# TP5400__2021-06-20.net
KiCad netlist of a schematic drawn in EasyEDA
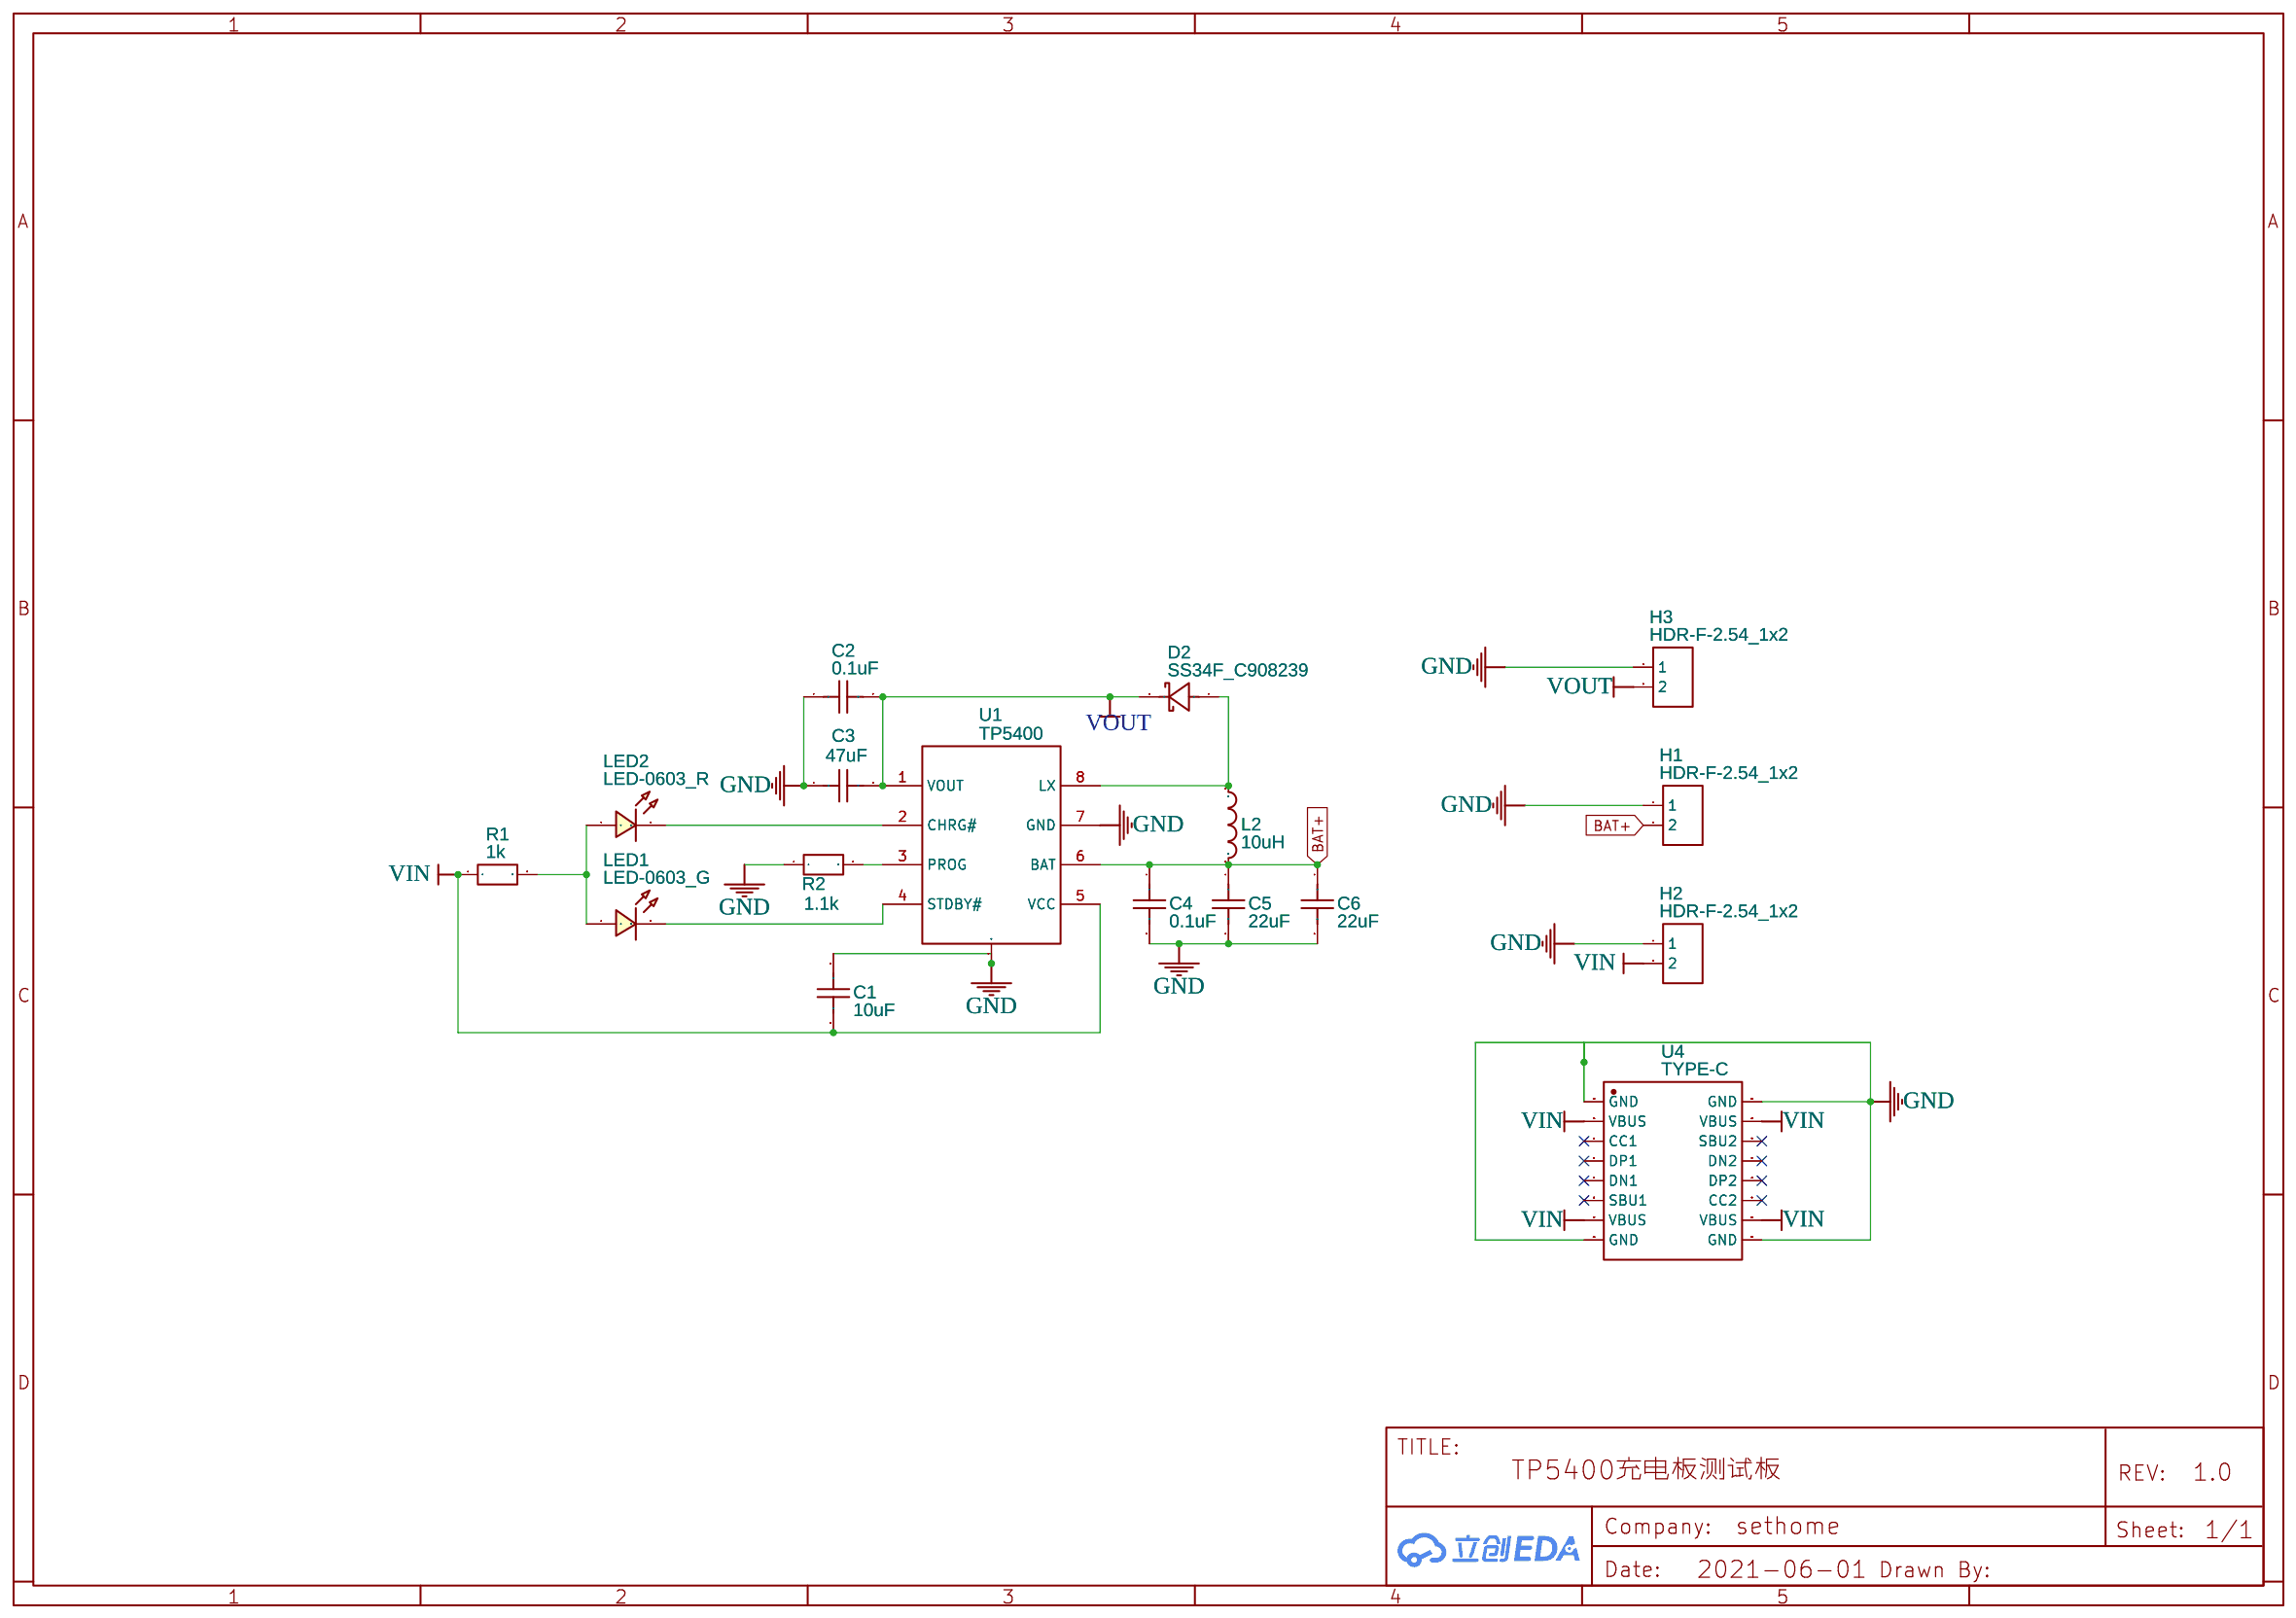
[diagram p0: schematic sheet]

(export (version "E")
  (design (tool "Eeschema 10.0.6"))
  (components
    (comp (ref "C1") (value "10uF") (libsource (lib "") (part "C_0603_US_1")))
    (comp (ref "C2") (value "0.1uF") (libsource (lib "") (part "C_0603_US")))
    (comp (ref "C3") (value "47uF") (libsource (lib "") (part "C_1206_US")))
    (comp (ref "C4") (value "0.1uF") (libsource (lib "") (part "C_0603_US_1")))
    (comp (ref "C5") (value "22uF") (libsource (lib "") (part "C_0603_US_1")))
    (comp (ref "C6") (value "22uF") (libsource (lib "") (part "C_0603_US_1")))
    (comp (ref "D2")
      (value "SS34F_C908239")
      (fields (field (name "BOM_Manufacturer Part") "SS34F") (field (name "BOM_Supplier Part") "C908239"))
      (libsource (lib "") (part "SS34F_C908239"))
    )
    (comp (ref "H1")
      (value "HDR-F-2.54_1x2")
      (fields (field (name "BOM_Supplier Part") "C49661"))
      (libsource (lib "") (part "HDR-F-2.54_1x2"))
    )
    (comp (ref "H2")
      (value "HDR-F-2.54_1x2")
      (fields (field (name "BOM_Supplier Part") "C49661"))
      (libsource (lib "") (part "HDR-F-2.54_1x2"))
    )
    (comp (ref "H3")
      (value "HDR-F-2.54_1x2")
      (fields (field (name "BOM_Supplier Part") "C49661"))
      (libsource (lib "") (part "HDR-F-2.54_1x2"))
    )
    (comp (ref "L2")
      (value "10uH")
      (fields
        (field (name "BOM_Manufacturer Part") "FXL0630-100-M")
        (field (name "BOM_Supplier Part") "C167223")
      )
      (libsource (lib "") (part "FXL0630-100-M"))
    )
    (comp (ref "LED1")
      (value "LED-0603_G")
      (fields
        (field (name "BOM_Manufacturer Part") "19-217/GHC-YR1S2/3T")
        (field (name "BOM_Supplier Part") "C72043")
      )
      (libsource (lib "") (part "LED-0603_G"))
    )
    (comp (ref "LED2")
      (value "LED-0603_R")
      (fields
        (field (name "BOM_Manufacturer Part") "19-217/R6C-AL1M2VY/3T")
        (field (name "BOM_Supplier Part") "C72044")
      )
      (libsource (lib "") (part "LED-0603_R"))
    )
    (comp (ref "R1") (value "1k") (libsource (lib "") (part "R_0603_EU")))
    (comp (ref "R2") (value "1.1k") (libsource (lib "") (part "R_0603_EU")))
    (comp (ref "U1")
      (value "TP5400")
      (fields (field (name "BOM_Supplier Part") "C24154"))
      (libsource (lib "") (part "TP5400"))
    )
    (comp (ref "U4") (value "TYPE-C") (libsource (lib "") (part "TYPE-C")))
  )
  (nets
    (net (code "1") (name "BAT+") (class "Default")
      (node (ref "C4") (pin "1") (pinfunction "1_1") (pintype "unspecified"))
      (node (ref "C5") (pin "1") (pinfunction "1_1") (pintype "unspecified"))
      (node (ref "C6") (pin "1") (pinfunction "1_1") (pintype "unspecified"))
      (node (ref "H1") (pin "2") (pinfunction "2_2") (pintype "input"))
      (node (ref "L2") (pin "2") (pinfunction "2_2") (pintype "unspecified"))
      (node (ref "U1") (pin "6") (pinfunction "BAT_6") (pintype "unspecified"))
    )
    (net (code "2") (name "GND") (class "Default")
      (node (ref "C1") (pin "1") (pinfunction "1_1") (pintype "unspecified"))
      (node (ref "C2") (pin "1") (pinfunction "1_1") (pintype "unspecified"))
      (node (ref "C3") (pin "1") (pinfunction "1_1") (pintype "unspecified"))
      (node (ref "C4") (pin "2") (pinfunction "2_2") (pintype "unspecified"))
      (node (ref "C5") (pin "2") (pinfunction "2_2") (pintype "unspecified"))
      (node (ref "C6") (pin "2") (pinfunction "2_2") (pintype "unspecified"))
      (node (ref "H1") (pin "1") (pinfunction "1_1") (pintype "input"))
      (node (ref "H2") (pin "1") (pinfunction "1_1") (pintype "input"))
      (node (ref "H3") (pin "1") (pinfunction "1_1") (pintype "input"))
      (node (ref "R2") (pin "1") (pinfunction "1_1") (pintype "unspecified"))
      (node (ref "U1") (pin "7") (pinfunction "GND_7") (pintype "unspecified"))
      (node (ref "U1") (pin "9") (pinfunction "9_9") (pintype "unspecified"))
      (node (ref "U4") (pin "A1/B12") (pinfunction "GND_A1/B12") (pintype "unspecified"))
      (node (ref "U4") (pin "B1/A12") (pinfunction "GND_B1/A12") (pintype "unspecified"))
    )
    (net (code "3") (name "Net-(D2-A)") (class "Default")
      (node (ref "D2") (pin "1") (pinfunction "A_1") (pintype "unspecified"))
      (node (ref "L2") (pin "1") (pinfunction "1_1") (pintype "unspecified"))
      (node (ref "U1") (pin "8") (pinfunction "LX_8") (pintype "unspecified"))
    )
    (net (code "4") (name "Net-(LED1-Pad1)") (class "Default")
      (node (ref "LED1") (pin "1") (pinfunction "1_1") (pintype "unspecified"))
      (node (ref "LED2") (pin "1") (pinfunction "1_1") (pintype "unspecified"))
      (node (ref "R1") (pin "2") (pinfunction "2_2") (pintype "unspecified"))
    )
    (net (code "5") (name "Net-(U1-CHRG#)") (class "Default")
      (node (ref "LED2") (pin "2") (pinfunction "2_2") (pintype "unspecified"))
      (node (ref "U1") (pin "2") (pinfunction "CHRG#_2") (pintype "unspecified"))
    )
    (net (code "6") (name "Net-(U1-PROG)") (class "Default")
      (node (ref "R2") (pin "2") (pinfunction "2_2") (pintype "unspecified"))
      (node (ref "U1") (pin "3") (pinfunction "PROG_3") (pintype "unspecified"))
    )
    (net (code "7") (name "Net-(U1-STDBY#)") (class "Default")
      (node (ref "LED1") (pin "2") (pinfunction "2_2") (pintype "unspecified"))
      (node (ref "U1") (pin "4") (pinfunction "STDBY#_4") (pintype "unspecified"))
    )
    (net (code "8") (name "VIN") (class "Default")
      (node (ref "C1") (pin "2") (pinfunction "2_2") (pintype "unspecified"))
      (node (ref "H2") (pin "2") (pinfunction "2_2") (pintype "input"))
      (node (ref "R1") (pin "1") (pinfunction "1_1") (pintype "unspecified"))
      (node (ref "U1") (pin "5") (pinfunction "VCC_5") (pintype "unspecified"))
      (node (ref "U4") (pin "A4/B9") (pinfunction "VBUS_A4/B9") (pintype "unspecified"))
      (node (ref "U4") (pin "B4/A9") (pinfunction "VBUS_B4/A9") (pintype "unspecified"))
    )
    (net (code "9") (name "VOUT") (class "Default")
      (node (ref "C2") (pin "2") (pinfunction "2_2") (pintype "unspecified"))
      (node (ref "C3") (pin "2") (pinfunction "2_2") (pintype "unspecified"))
      (node (ref "D2") (pin "2") (pinfunction "K_2") (pintype "unspecified"))
      (node (ref "H3") (pin "2") (pinfunction "2_2") (pintype "input"))
      (node (ref "U1") (pin "1") (pinfunction "VOUT_1") (pintype "unspecified"))
    )
    (net (code "10") (name "unconnected-(U4-CC1-PadA5)") (class "Default")
      (node (ref "U4") (pin "A5") (pinfunction "CC1_A5") (pintype "unspecified+no_connect"))
    )
    (net (code "11") (name "unconnected-(U4-CC2-PadB5)") (class "Default")
      (node (ref "U4") (pin "B5") (pinfunction "CC2_B5") (pintype "unspecified+no_connect"))
    )
    (net (code "12") (name "unconnected-(U4-DN1-PadA7)") (class "Default")
      (node (ref "U4") (pin "A7") (pinfunction "DN1_A7") (pintype "unspecified+no_connect"))
    )
    (net (code "13") (name "unconnected-(U4-DN2-PadB7)") (class "Default")
      (node (ref "U4") (pin "B7") (pinfunction "DN2_B7") (pintype "unspecified+no_connect"))
    )
    (net (code "14") (name "unconnected-(U4-DP1-PadA6)") (class "Default")
      (node (ref "U4") (pin "A6") (pinfunction "DP1_A6") (pintype "unspecified+no_connect"))
    )
    (net (code "15") (name "unconnected-(U4-DP2-PadB6)") (class "Default")
      (node (ref "U4") (pin "B6") (pinfunction "DP2_B6") (pintype "unspecified+no_connect"))
    )
    (net (code "16") (name "unconnected-(U4-SBU1-PadA8)") (class "Default")
      (node (ref "U4") (pin "A8") (pinfunction "SBU1_A8") (pintype "unspecified+no_connect"))
    )
    (net (code "17") (name "unconnected-(U4-SBU2-PadB8)") (class "Default")
      (node (ref "U4") (pin "B8") (pinfunction "SBU2_B8") (pintype "unspecified+no_connect"))
    )
  )
)
